# fan_ctrl.net
KiCad netlist of a schematic drawn in Altium Designer
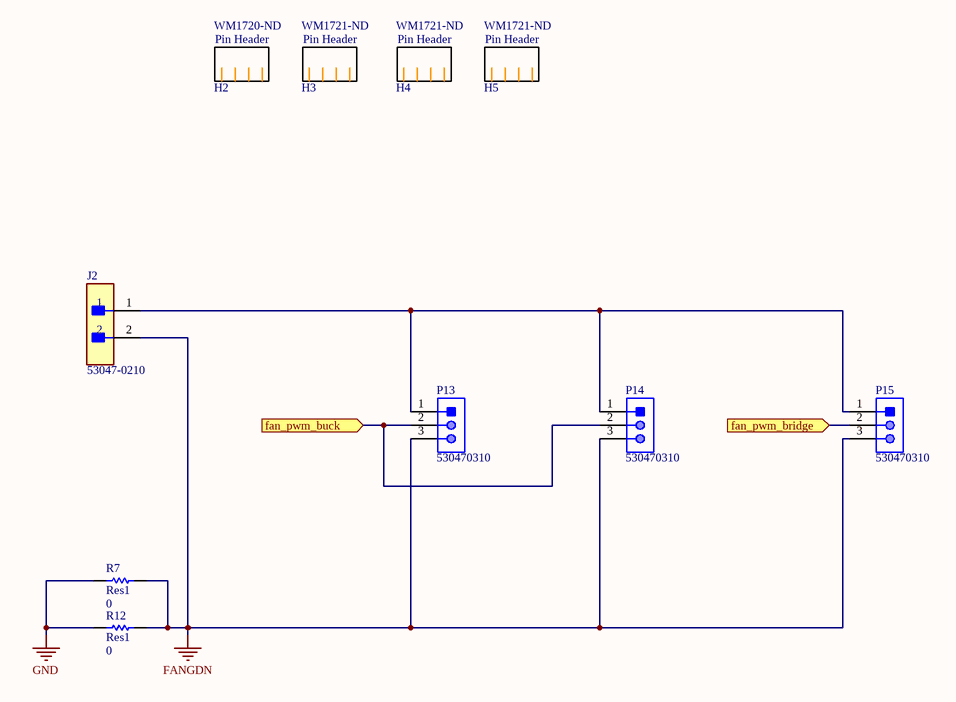
[diagram p0: fan_ctrl.SchDoc]

(export (version "E")
  (design (tool "Eeschema 10.0.6"))
  (components
    (comp (ref "H2")
      (value "Generic Pin  Header")
      (description "Assign Supplier Link Manually")
      (fields (field (name "SUPPLIER PART NUMBER 1") "WM1720-ND"))
      (libsource (lib "coil_driver_lib") (part "generic_pin_header"))
    )
    (comp (ref "H3")
      (value "Generic Pin  Header")
      (description "Assign Supplier Link Manually")
      (fields (field (name "SUPPLIER PART NUMBER 1") "WM1721-ND"))
      (libsource (lib "coil_driver_lib") (part "generic_pin_header"))
    )
    (comp (ref "H4")
      (value "Generic Pin  Header")
      (description "Assign Supplier Link Manually")
      (fields (field (name "SUPPLIER PART NUMBER 1") "WM1721-ND"))
      (libsource (lib "coil_driver_lib") (part "generic_pin_header"))
    )
    (comp (ref "H5")
      (value "Generic Pin  Header")
      (description "Assign Supplier Link Manually")
      (fields (field (name "SUPPLIER PART NUMBER 1") "WM1721-ND"))
      (libsource (lib "coil_driver_lib") (part "generic_pin_header"))
    )
    (comp (ref "J2")
      (value "53047-0210")
      (footprint "FP-53047-0210-MFG")
      (description "CONN HEADER VERT 2POS 1.25MM")
      (fields
        (field (name "OCTOPART") "https://octopart.com/53047-0210-molex-276772")
        (field (name "MANUFACTURER") "Molex")
      )
      (libsource (lib "Altium Content Vault") (part "3bc925449376181038e59eaffc5286c"))
    )
    (comp (ref "P13")
      (value "530470310")
      (footprint "MOLX-530470310_V")
      (fields (field (name "MANUFACTURER") "Molex"))
      (libsource (lib "Altium Content Vault") (part "CN-1P-M-R3"))
    )
    (comp (ref "P14")
      (value "530470310")
      (footprint "MOLX-530470310_V")
      (fields (field (name "MANUFACTURER") "Molex"))
      (libsource (lib "Altium Content Vault") (part "CN-1P-M-R3"))
    )
    (comp (ref "P15")
      (value "530470310")
      (footprint "MOLX-530470310_V")
      (fields (field (name "MANUFACTURER") "Molex"))
      (libsource (lib "Altium Content Vault") (part "CN-1P-M-R3"))
    )
    (comp (ref "R7")
      (value "Res1")
      (footprint "RES 0603_1608")
      (description "Resistor")
      (fields (field (name "ALTIUM_VALUE") "0") (field (name "PUBLISHER") "Altium Limited"))
      (libsource (lib "Miscellaneous Devices") (part "Res1"))
    )
    (comp (ref "R12")
      (value "Res1")
      (footprint "RES 0603_1608")
      (description "Resistor")
      (fields (field (name "ALTIUM_VALUE") "0") (field (name "PUBLISHER") "Altium Limited"))
      (libsource (lib "Miscellaneous Devices") (part "Res1"))
    )
  )
  (nets
    (net (code "1") (name "/fan_pwm_bridge") (class "Default")
      (node (ref "P15") (pin "2") (pinfunction "2_2") (pintype "passive"))
    )
    (net (code "2") (name "/fan_pwm_buck") (class "Default")
      (node (ref "P13") (pin "2") (pinfunction "2_2") (pintype "passive"))
      (node (ref "P14") (pin "2") (pinfunction "2_2") (pintype "passive"))
    )
    (net (code "3") (name "FANGDN") (class "Default")
      (node (ref "J2") (pin "2") (pinfunction "2_2") (pintype "passive"))
      (node (ref "P13") (pin "3") (pinfunction "3_3") (pintype "passive"))
      (node (ref "P14") (pin "3") (pinfunction "3_3") (pintype "passive"))
      (node (ref "P15") (pin "3") (pinfunction "3_3") (pintype "passive"))
      (node (ref "R12") (pin "2") (pinfunction "2_2") (pintype "passive"))
      (node (ref "R7") (pin "2") (pinfunction "2_2") (pintype "passive"))
    )
    (net (code "4") (name "GND") (class "Default")
      (node (ref "R12") (pin "1") (pinfunction "1_1") (pintype "passive"))
      (node (ref "R7") (pin "1") (pinfunction "1_1") (pintype "passive"))
    )
    (net (code "5") (name "Net-(J2-Pad1)") (class "Default")
      (node (ref "J2") (pin "1") (pinfunction "1_1") (pintype "passive"))
      (node (ref "P13") (pin "1") (pinfunction "1_1") (pintype "passive"))
      (node (ref "P14") (pin "1") (pinfunction "1_1") (pintype "passive"))
      (node (ref "P15") (pin "1") (pinfunction "1_1") (pintype "passive"))
    )
  )
)
